# L1221_TOP_V2_3.net
KiCad netlist of a schematic drawn in Altium Designer
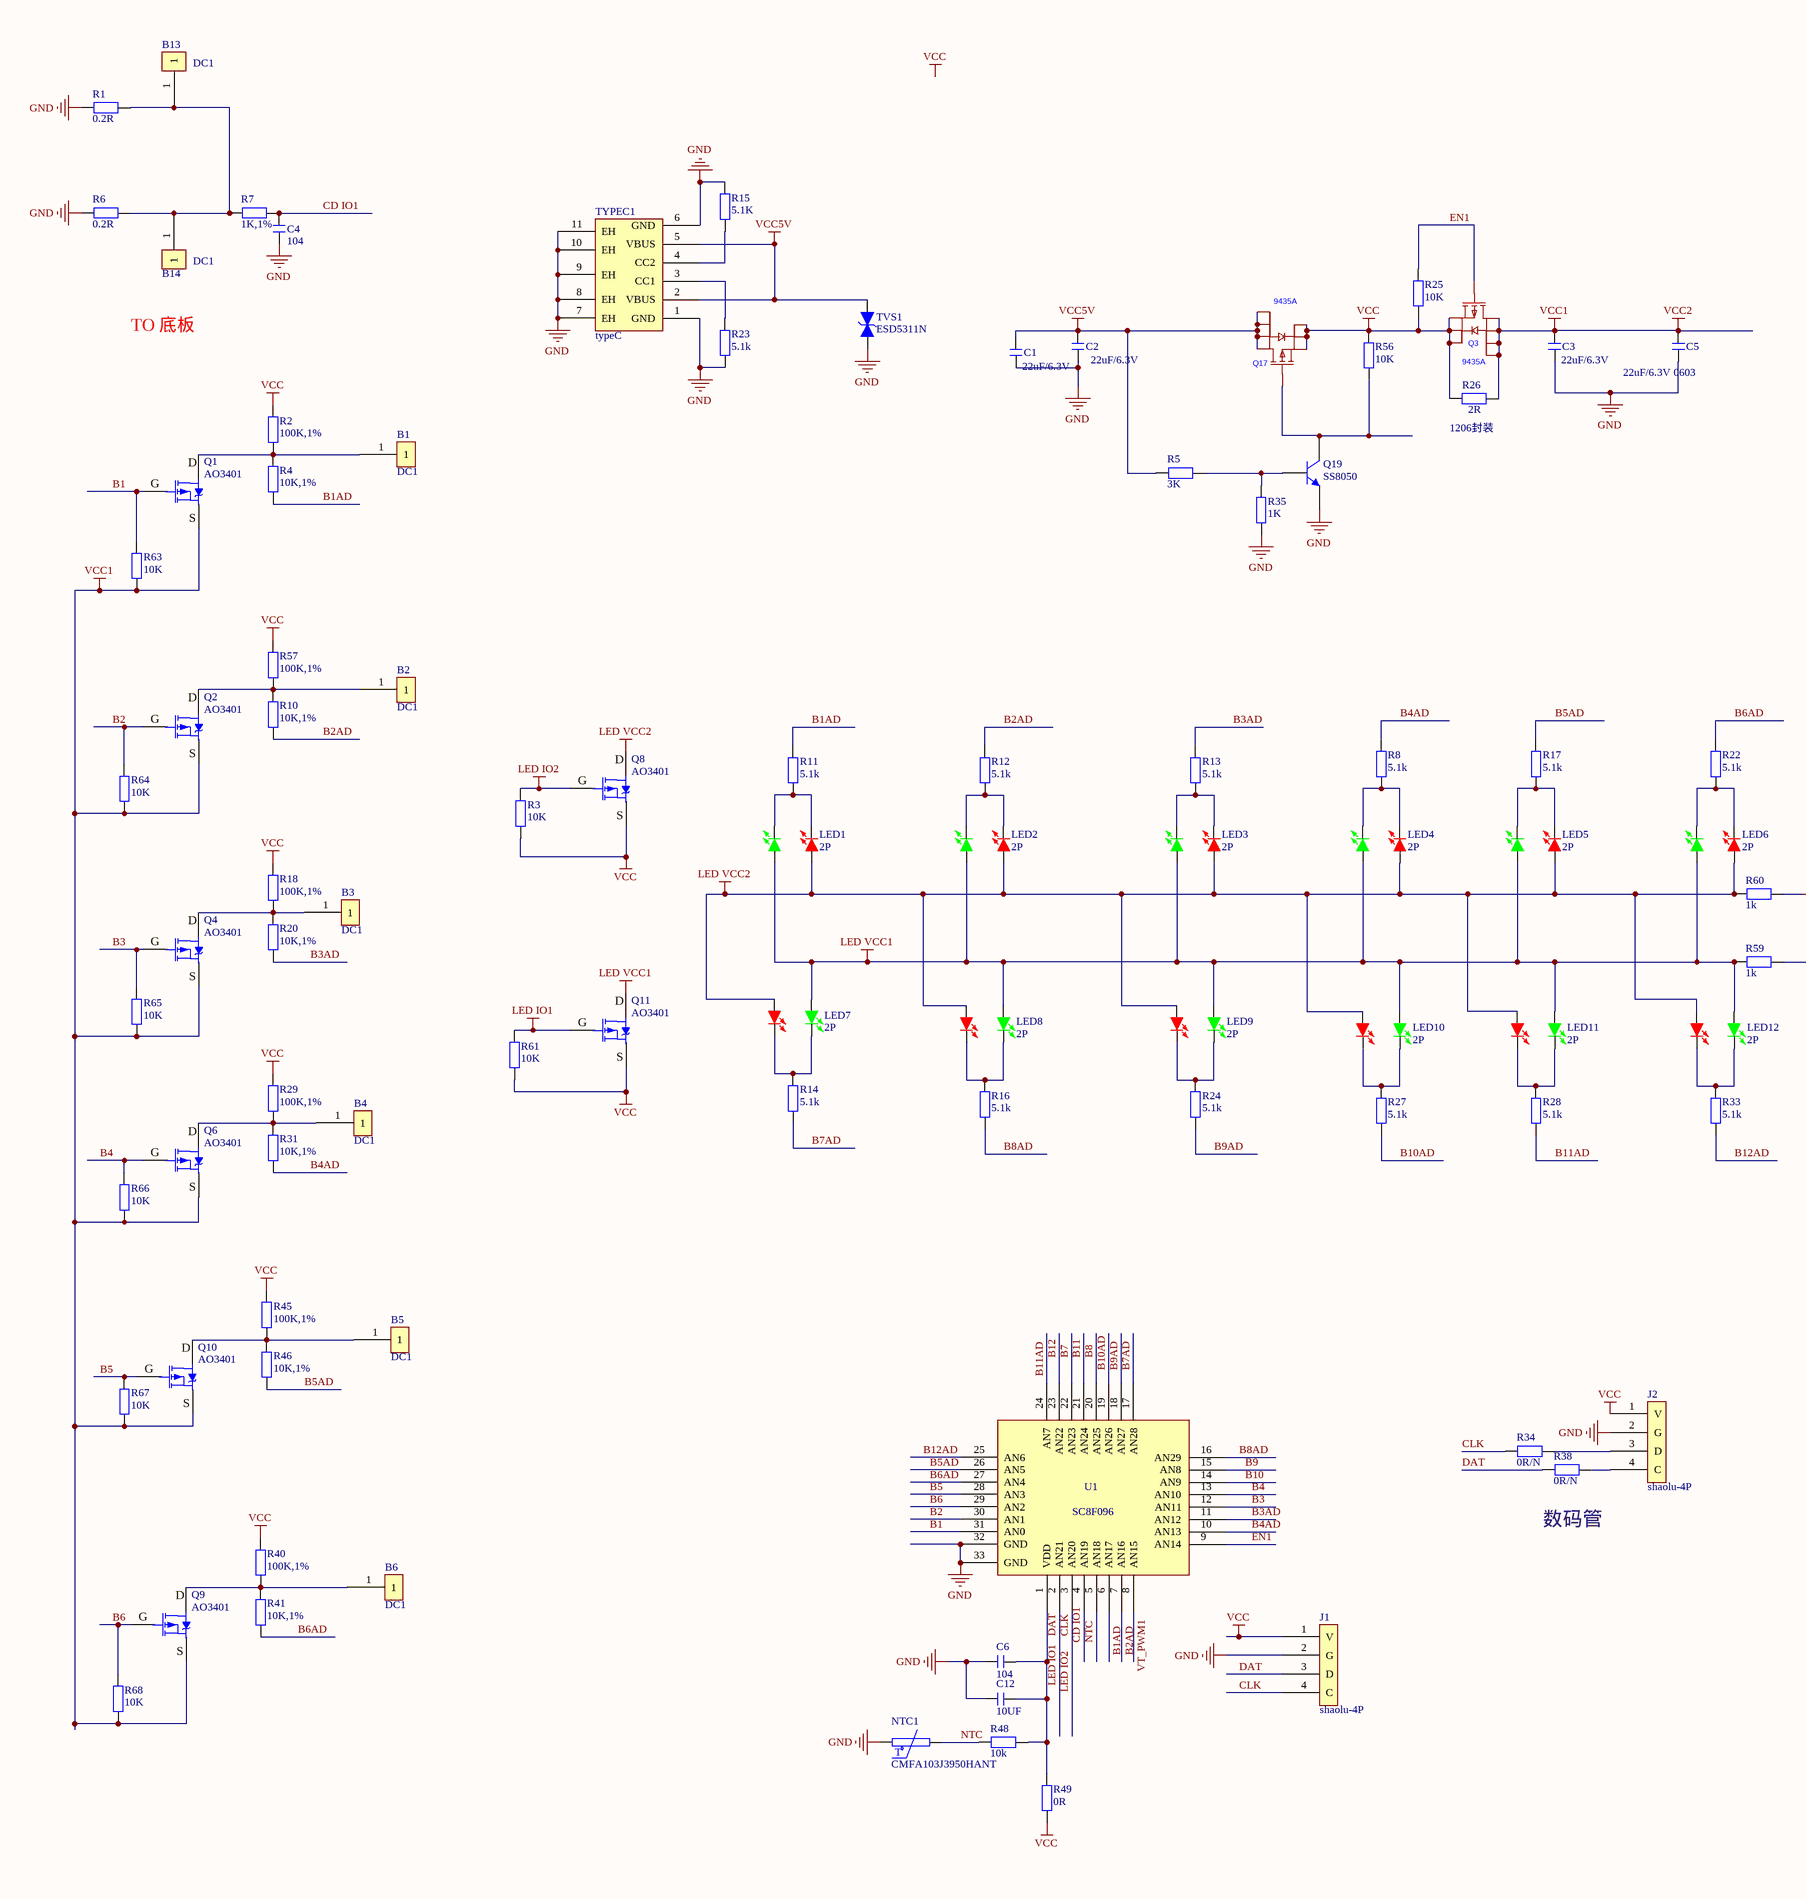
[diagram p0: L1221 TOP V2.3.SchDoc, left]
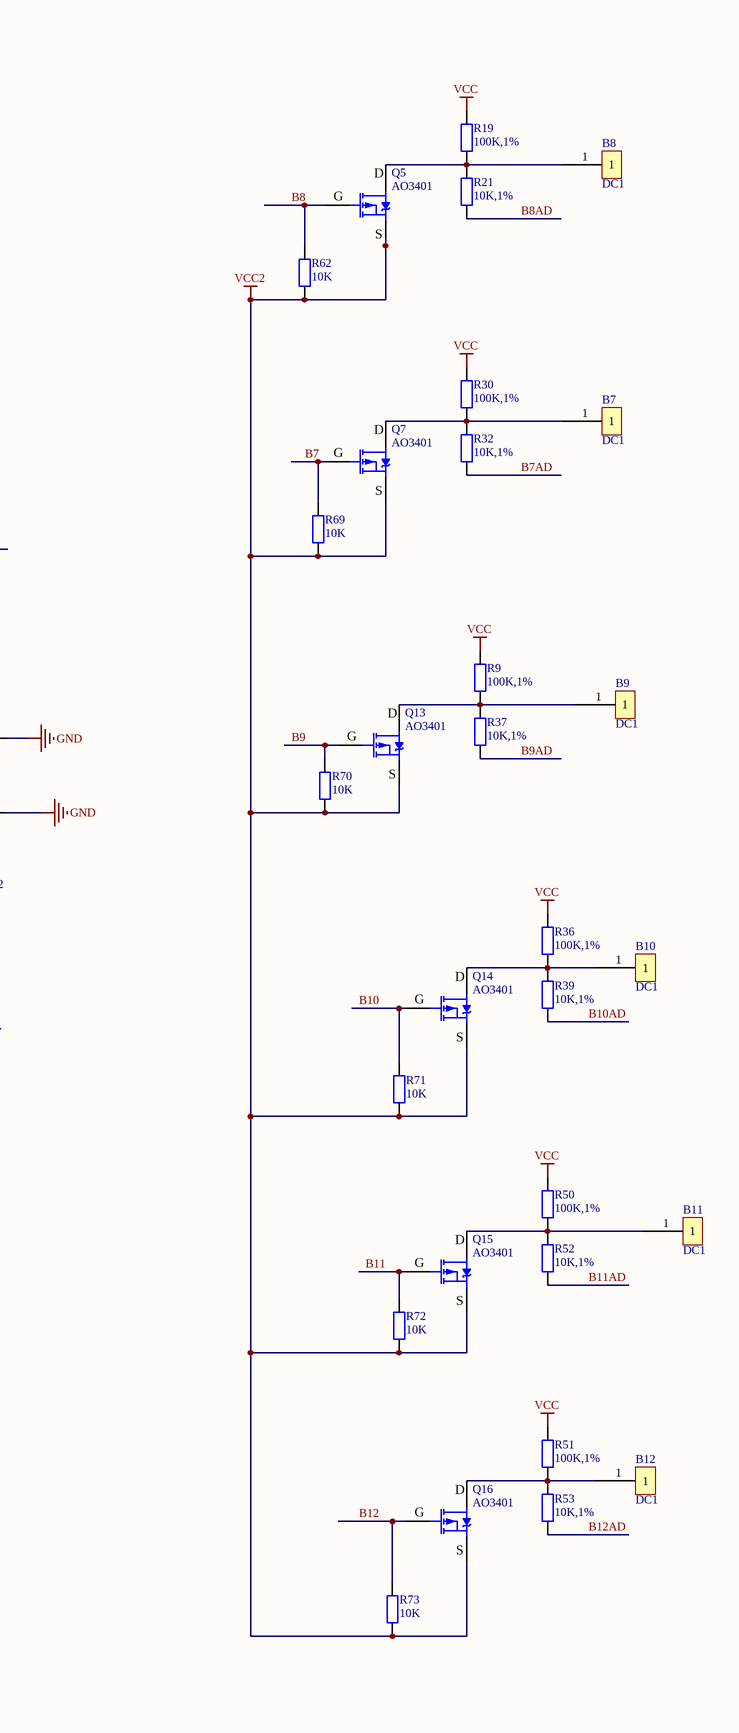
[diagram p1: L1221 TOP V2.3.SchDoc, right]

(export (version "E")
  (design (tool "Eeschema 10.0.6"))
  (components
    (comp (ref "B1") (value "DC1") (footprint "POPOPIN01") (libsource (lib "") (part "dianchi1_1")))
    (comp (ref "B2") (value "DC1") (footprint "POPOPIN01") (libsource (lib "") (part "dianchi1_1")))
    (comp (ref "B3") (value "DC1") (footprint "POPOPIN01") (libsource (lib "") (part "dianchi1_1")))
    (comp (ref "B4") (value "DC1") (footprint "POPOPIN01") (libsource (lib "") (part "dianchi1_1")))
    (comp (ref "B5") (value "DC1") (footprint "POPOPIN01") (libsource (lib "") (part "dianchi1_1")))
    (comp (ref "B6") (value "DC1") (footprint "POPOPIN01") (libsource (lib "") (part "dianchi1_1")))
    (comp (ref "B7") (value "DC1") (footprint "POPOPIN01") (libsource (lib "") (part "dianchi1_1")))
    (comp (ref "B8") (value "DC1") (footprint "POPOPIN01") (libsource (lib "") (part "dianchi1_1")))
    (comp (ref "B9") (value "DC1") (footprint "POPOPIN01") (libsource (lib "") (part "dianchi1_1")))
    (comp (ref "B10") (value "DC1") (footprint "POPOPIN01") (libsource (lib "") (part "dianchi1_1")))
    (comp (ref "B11") (value "DC1") (footprint "POPOPIN01") (libsource (lib "") (part "dianchi1_1")))
    (comp (ref "B12") (value "DC1") (footprint "POPOPIN01") (libsource (lib "") (part "dianchi1_1")))
    (comp (ref "B13") (value "DC1") (footprint "POPOPIN01") (libsource (lib "4.1   - 接口类") (part "dianchi1")))
    (comp (ref "B14") (value "DC1") (footprint "POPOPIN01") (libsource (lib "") (part "dianchi1_2")))
    (comp (ref "C1")
      (value "22uF/6.3V")
      (footprint "0805L")
      (description "无极性贴片电容")
      (libsource (lib "3.1   - 电阻-电容-电感") (part "C"))
    )
    (comp (ref "C2")
      (value "22uF/6.3V")
      (footprint "0805l")
      (description "无极性贴片电容")
      (libsource (lib "3.1   - 电阻-电容-电感") (part "C"))
    )
    (comp (ref "C3")
      (value "22uF/6.3V")
      (footprint "0805l")
      (description "无极性贴片电容")
      (libsource (lib "3.1   - 电阻-电容-电感") (part "C"))
    )
    (comp (ref "C4")
      (value "104")
      (footprint "R0402")
      (description "无极性贴片电容")
      (libsource (lib "3.1   - 电阻-电容-电感") (part "C"))
    )
    (comp (ref "C5")
      (value "22uF/6.3V 0603")
      (footprint "0805l")
      (description "无极性贴片电容")
      (libsource (lib "3.1   - 电阻-电容-电感") (part "C"))
    )
    (comp (ref "C6")
      (value "104")
      (footprint "R0402")
      (description "无极性贴片电容")
      (libsource (lib "3.1   - 电阻-电容-电感") (part "C"))
    )
    (comp (ref "C12")
      (value "10UF")
      (footprint "0603L")
      (description "无极性贴片电容")
      (libsource (lib "3.1   - 电阻-电容-电感") (part "C"))
    )
    (comp (ref "J1")
      (value "shaolu-4P")
      (footprint "shaolu-4P")
      (libsource (lib "4.1   - 接口类") (part "shaolu-4P"))
    )
    (comp (ref "J2")
      (value "shaolu-4P")
      (footprint "W60.5-L48数码管")
      (libsource (lib "4.1   - 接口类") (part "shaolu-4P"))
    )
    (comp (ref "LED1")
      (value "2P")
      (footprint "LED 0606")
      (description "共阴双色LED")
      (libsource (lib "9.1   - LED") (part "LED RG-K"))
    )
    (comp (ref "LED2")
      (value "2P")
      (footprint "LED 0606")
      (description "共阴双色LED")
      (libsource (lib "9.1   - LED") (part "LED RG-K"))
    )
    (comp (ref "LED3")
      (value "2P")
      (footprint "LED 0606")
      (description "共阴双色LED")
      (libsource (lib "9.1   - LED") (part "LED RG-K"))
    )
    (comp (ref "LED4")
      (value "2P")
      (footprint "LED 0606")
      (description "共阴双色LED")
      (libsource (lib "9.1   - LED") (part "LED RG-K"))
    )
    (comp (ref "LED5")
      (value "2P")
      (footprint "LED 0606")
      (description "共阴双色LED")
      (libsource (lib "9.1   - LED") (part "LED RG-K"))
    )
    (comp (ref "LED6")
      (value "2P")
      (footprint "LED 0606")
      (description "共阴双色LED")
      (libsource (lib "9.1   - LED") (part "LED RG-K"))
    )
    (comp (ref "LED7")
      (value "2P")
      (footprint "LED 0606")
      (description "共阴双色LED")
      (libsource (lib "9.1   - LED") (part "LED RG-K"))
    )
    (comp (ref "LED8")
      (value "2P")
      (footprint "LED 0606")
      (description "共阴双色LED")
      (libsource (lib "9.1   - LED") (part "LED RG-K"))
    )
    (comp (ref "LED9")
      (value "2P")
      (footprint "LED 0606")
      (description "共阴双色LED")
      (libsource (lib "9.1   - LED") (part "LED RG-K"))
    )
    (comp (ref "LED10")
      (value "2P")
      (footprint "LED 0606")
      (description "共阴双色LED")
      (libsource (lib "9.1   - LED") (part "LED RG-K"))
    )
    (comp (ref "LED11")
      (value "2P")
      (footprint "LED 0606")
      (description "共阴双色LED")
      (libsource (lib "9.1   - LED") (part "LED RG-K"))
    )
    (comp (ref "LED12")
      (value "2P")
      (footprint "LED 0606")
      (description "共阴双色LED")
      (libsource (lib "9.1   - LED") (part "LED RG-K"))
    )
    (comp (ref "NTC1") (value "CMFA103J3950HANT") (footprint "0603L") (libsource (lib "*") (part "RES2-R")))
    (comp (ref "Q1")
      (value "AO3401")
      (footprint "SOT23-3N")
      (description "P沟道场效应管")
      (libsource (lib "6.1   - 场效应管-可控硅") (part "SI2301"))
    )
    (comp (ref "Q2")
      (value "AO3401")
      (footprint "SOT23-3N")
      (description "P沟道场效应管")
      (libsource (lib "6.1   - 场效应管-可控硅") (part "SI2301"))
    )
    (comp (ref "Q3")
      (value "9435A")
      (footprint "SOP8")
      (fields (field (name "MANUFACTURER") "HL(富海微)"))
      (libsource (lib "altium-import") (part "root_3_9435A_"))
    )
    (comp (ref "Q4")
      (value "AO3401")
      (footprint "SOT23-3N")
      (description "P沟道场效应管")
      (libsource (lib "6.1   - 场效应管-可控硅") (part "SI2301"))
    )
    (comp (ref "Q5")
      (value "AO3401")
      (footprint "SOT23-3N")
      (description "P沟道场效应管")
      (libsource (lib "6.1   - 场效应管-可控硅") (part "SI2301"))
    )
    (comp (ref "Q6")
      (value "AO3401")
      (footprint "SOT23-3N")
      (description "P沟道场效应管")
      (libsource (lib "6.1   - 场效应管-可控硅") (part "SI2301"))
    )
    (comp (ref "Q7")
      (value "AO3401")
      (footprint "SOT23-3N")
      (description "P沟道场效应管")
      (libsource (lib "6.1   - 场效应管-可控硅") (part "SI2301"))
    )
    (comp (ref "Q8")
      (value "AO3401")
      (footprint "SOT23-3N")
      (description "P沟道场效应管")
      (libsource (lib "6.1   - 场效应管-可控硅") (part "SI2301"))
    )
    (comp (ref "Q9")
      (value "AO3401")
      (footprint "SOT23-3N")
      (description "P沟道场效应管")
      (libsource (lib "6.1   - 场效应管-可控硅") (part "SI2301"))
    )
    (comp (ref "Q10")
      (value "AO3401")
      (footprint "SOT23-3N")
      (description "P沟道场效应管")
      (libsource (lib "6.1   - 场效应管-可控硅") (part "SI2301"))
    )
    (comp (ref "Q11")
      (value "AO3401")
      (footprint "SOT23-3N")
      (description "P沟道场效应管")
      (libsource (lib "6.1   - 场效应管-可控硅") (part "SI2301"))
    )
    (comp (ref "Q13")
      (value "AO3401")
      (footprint "SOT23-3N")
      (description "P沟道场效应管")
      (libsource (lib "6.1   - 场效应管-可控硅") (part "SI2301"))
    )
    (comp (ref "Q14")
      (value "AO3401")
      (footprint "SOT23-3N")
      (description "P沟道场效应管")
      (libsource (lib "6.1   - 场效应管-可控硅") (part "SI2301"))
    )
    (comp (ref "Q15")
      (value "AO3401")
      (footprint "SOT23-3N")
      (description "P沟道场效应管")
      (libsource (lib "6.1   - 场效应管-可控硅") (part "SI2301"))
    )
    (comp (ref "Q16")
      (value "AO3401")
      (footprint "SOT23-3N")
      (description "P沟道场效应管")
      (libsource (lib "6.1   - 场效应管-可控硅") (part "SI2301"))
    )
    (comp (ref "Q17")
      (value "9435A")
      (footprint "SOP8")
      (fields (field (name "MANUFACTURER") "HL(富海微)"))
      (libsource (lib "altium-import") (part "root_1_9435A_"))
    )
    (comp (ref "Q19")
      (value "SS8050")
      (footprint "SOT23-3N")
      (description "NPN Bipolar Transistor")
      (libsource (lib "Miscellaneous Devices") (part "QNPN"))
    )
    (comp (ref "R1")
      (value "0.2R")
      (footprint "R 1206_L")
      (description "贴片电阻")
      (libsource (lib "3.1   - 电阻-电容-电感") (part "R"))
    )
    (comp (ref "R2")
      (value "100K,1%")
      (footprint "R0402")
      (description "贴片电阻")
      (fields (field (name "TOLERANCE") "±5%"))
      (libsource (lib "3.1   - 电阻-电容-电感") (part "R"))
    )
    (comp (ref "R3")
      (value "10K")
      (footprint "R0402")
      (description "贴片电阻")
      (fields (field (name "TOLERANCE") "±5%") (field (name "TOLERANCE_1") "Tolerance"))
      (libsource (lib "3.1   - 电阻-电容-电感") (part "R"))
    )
    (comp (ref "R4")
      (value "10K,1%")
      (footprint "R0402")
      (description "贴片电阻")
      (fields (field (name "TOLERANCE") "±1%"))
      (libsource (lib "3.1   - 电阻-电容-电感") (part "R"))
    )
    (comp (ref "R5")
      (value "3K")
      (footprint "R0402")
      (description "贴片电阻")
      (libsource (lib "3.1   - 电阻-电容-电感") (part "R"))
    )
    (comp (ref "R6")
      (value "0.2R")
      (footprint "R 1206_L")
      (description "贴片电阻")
      (libsource (lib "3.1   - 电阻-电容-电感") (part "R"))
    )
    (comp (ref "R7")
      (value "1K,1%")
      (footprint "R0402")
      (description "贴片电阻")
      (libsource (lib "3.1   - 电阻-电容-电感") (part "R"))
    )
    (comp (ref "R8")
      (value "5.1k")
      (footprint "R0402")
      (description "贴片电阻")
      (fields (field (name "TOLERANCE") "±5%") (field (name "TOLERANCE_1") "Tolerance"))
      (libsource (lib "3.1   - 电阻-电容-电感") (part "R"))
    )
    (comp (ref "R9")
      (value "100K,1%")
      (footprint "R0402")
      (description "贴片电阻")
      (fields (field (name "TOLERANCE") "±5%"))
      (libsource (lib "3.1   - 电阻-电容-电感") (part "R"))
    )
    (comp (ref "R10")
      (value "10K,1%")
      (footprint "R0402")
      (description "贴片电阻")
      (fields (field (name "TOLERANCE") "±1%"))
      (libsource (lib "3.1   - 电阻-电容-电感") (part "R"))
    )
    (comp (ref "R11")
      (value "5.1k")
      (footprint "R0402")
      (description "贴片电阻")
      (fields (field (name "TOLERANCE") "±5%") (field (name "TOLERANCE_1") "Tolerance"))
      (libsource (lib "3.1   - 电阻-电容-电感") (part "R"))
    )
    (comp (ref "R12")
      (value "5.1k")
      (footprint "R0402")
      (description "贴片电阻")
      (fields (field (name "TOLERANCE") "±5%") (field (name "TOLERANCE_1") "Tolerance"))
      (libsource (lib "3.1   - 电阻-电容-电感") (part "R"))
    )
    (comp (ref "R13")
      (value "5.1k")
      (footprint "R0402")
      (description "贴片电阻")
      (fields (field (name "TOLERANCE") "±5%") (field (name "TOLERANCE_1") "Tolerance"))
      (libsource (lib "3.1   - 电阻-电容-电感") (part "R"))
    )
    (comp (ref "R14")
      (value "5.1k")
      (footprint "R0402")
      (description "贴片电阻")
      (fields (field (name "TOLERANCE") "±5%") (field (name "TOLERANCE_1") "Tolerance"))
      (libsource (lib "3.1   - 电阻-电容-电感") (part "R"))
    )
    (comp (ref "R15")
      (value "5.1K")
      (footprint "r0402")
      (description "贴片电阻")
      (libsource (lib "3.1   - 电阻-电容-电感") (part "R"))
    )
    (comp (ref "R16")
      (value "5.1k")
      (footprint "R0402")
      (description "贴片电阻")
      (fields (field (name "TOLERANCE") "±5%") (field (name "TOLERANCE_1") "Tolerance"))
      (libsource (lib "3.1   - 电阻-电容-电感") (part "R"))
    )
    (comp (ref "R17")
      (value "5.1k")
      (footprint "R0402")
      (description "贴片电阻")
      (fields (field (name "TOLERANCE") "±5%") (field (name "TOLERANCE_1") "Tolerance"))
      (libsource (lib "3.1   - 电阻-电容-电感") (part "R"))
    )
    (comp (ref "R18")
      (value "100K,1%")
      (footprint "R0402")
      (description "贴片电阻")
      (fields (field (name "TOLERANCE") "Tolerance") (field (name "TOLERANCE_1") "±5%"))
      (libsource (lib "3.1   - 电阻-电容-电感") (part "R"))
    )
    (comp (ref "R19")
      (value "100K,1%")
      (footprint "R0402")
      (description "贴片电阻")
      (fields (field (name "TOLERANCE") "±5%"))
      (libsource (lib "3.1   - 电阻-电容-电感") (part "R"))
    )
    (comp (ref "R20")
      (value "10K,1%")
      (footprint "R0402")
      (description "贴片电阻")
      (fields (field (name "TOLERANCE") "±1%"))
      (libsource (lib "3.1   - 电阻-电容-电感") (part "R"))
    )
    (comp (ref "R21")
      (value "10K,1%")
      (footprint "R0402")
      (description "贴片电阻")
      (fields (field (name "TOLERANCE") "±1%"))
      (libsource (lib "3.1   - 电阻-电容-电感") (part "R"))
    )
    (comp (ref "R22")
      (value "5.1k")
      (footprint "R0402")
      (description "贴片电阻")
      (fields (field (name "TOLERANCE") "±5%") (field (name "TOLERANCE_1") "Tolerance"))
      (libsource (lib "3.1   - 电阻-电容-电感") (part "R"))
    )
    (comp (ref "R23")
      (value "5.1k")
      (footprint "R0402")
      (description "贴片电阻")
      (libsource (lib "3.1   - 电阻-电容-电感") (part "R"))
    )
    (comp (ref "R24")
      (value "5.1k")
      (footprint "R0402")
      (description "贴片电阻")
      (fields (field (name "TOLERANCE") "±5%") (field (name "TOLERANCE_1") "Tolerance"))
      (libsource (lib "3.1   - 电阻-电容-电感") (part "R"))
    )
    (comp (ref "R25")
      (value "10K")
      (footprint "R0402")
      (description "贴片电阻")
      (fields (field (name "TOLERANCE") "±5%"))
      (libsource (lib "3.1   - 电阻-电容-电感") (part "R"))
    )
    (comp (ref "R26")
      (value "2R")
      (footprint "R 1206_L")
      (description "贴片电阻")
      (fields (field (name "TOLERANCE") "±5%"))
      (libsource (lib "3.1   - 电阻-电容-电感") (part "R"))
    )
    (comp (ref "R27")
      (value "5.1k")
      (footprint "R0402")
      (description "贴片电阻")
      (fields (field (name "TOLERANCE") "±5%") (field (name "TOLERANCE_1") "Tolerance"))
      (libsource (lib "3.1   - 电阻-电容-电感") (part "R"))
    )
    (comp (ref "R28")
      (value "5.1k")
      (footprint "R0402")
      (description "贴片电阻")
      (fields (field (name "TOLERANCE") "±5%") (field (name "TOLERANCE_1") "Tolerance"))
      (libsource (lib "3.1   - 电阻-电容-电感") (part "R"))
    )
    (comp (ref "R29")
      (value "100K,1%")
      (footprint "R0402")
      (description "贴片电阻")
      (fields (field (name "TOLERANCE") "±5%"))
      (libsource (lib "3.1   - 电阻-电容-电感") (part "R"))
    )
    (comp (ref "R30")
      (value "100K,1%")
      (footprint "R0402")
      (description "贴片电阻")
      (fields (field (name "TOLERANCE") "±5%"))
      (libsource (lib "3.1   - 电阻-电容-电感") (part "R"))
    )
    (comp (ref "R31")
      (value "10K,1%")
      (footprint "R0402")
      (description "贴片电阻")
      (fields (field (name "TOLERANCE") "±1%"))
      (libsource (lib "3.1   - 电阻-电容-电感") (part "R"))
    )
    (comp (ref "R32")
      (value "10K,1%")
      (footprint "R0402")
      (description "贴片电阻")
      (fields (field (name "TOLERANCE") "±1%"))
      (libsource (lib "3.1   - 电阻-电容-电感") (part "R"))
    )
    (comp (ref "R33")
      (value "5.1k")
      (footprint "R0402")
      (description "贴片电阻")
      (fields (field (name "TOLERANCE") "±5%") (field (name "TOLERANCE_1") "Tolerance"))
      (libsource (lib "3.1   - 电阻-电容-电感") (part "R"))
    )
    (comp (ref "R34")
      (value "0R/N")
      (footprint "R0402")
      (description "贴片电阻")
      (libsource (lib "3.1   - 电阻-电容-电感") (part "R"))
    )
    (comp (ref "R35")
      (value "1K")
      (footprint "R0402")
      (description "贴片电阻")
      (libsource (lib "3.1   - 电阻-电容-电感") (part "R"))
    )
    (comp (ref "R36")
      (value "100K,1%")
      (footprint "R0402")
      (description "贴片电阻")
      (fields (field (name "TOLERANCE") "±5%"))
      (libsource (lib "3.1   - 电阻-电容-电感") (part "R"))
    )
    (comp (ref "R37")
      (value "10K,1%")
      (footprint "R0402")
      (description "贴片电阻")
      (fields (field (name "TOLERANCE") "±1%"))
      (libsource (lib "3.1   - 电阻-电容-电感") (part "R"))
    )
    (comp (ref "R38")
      (value "0R/N")
      (footprint "R0402")
      (description "贴片电阻")
      (libsource (lib "3.1   - 电阻-电容-电感") (part "R"))
    )
    (comp (ref "R39")
      (value "10K,1%")
      (footprint "R0402")
      (description "贴片电阻")
      (fields (field (name "TOLERANCE") "±1%"))
      (libsource (lib "3.1   - 电阻-电容-电感") (part "R"))
    )
    (comp (ref "R40")
      (value "100K,1%")
      (footprint "R0402")
      (description "贴片电阻")
      (fields (field (name "TOLERANCE") "±5%"))
      (libsource (lib "3.1   - 电阻-电容-电感") (part "R"))
    )
    (comp (ref "R41")
      (value "10K,1%")
      (footprint "R0402")
      (description "贴片电阻")
      (fields (field (name "TOLERANCE") "±1%"))
      (libsource (lib "3.1   - 电阻-电容-电感") (part "R"))
    )
    (comp (ref "R45")
      (value "100K,1%")
      (footprint "R0402")
      (description "贴片电阻")
      (fields (field (name "TOLERANCE") "±5%"))
      (libsource (lib "3.1   - 电阻-电容-电感") (part "R"))
    )
    (comp (ref "R46")
      (value "10K,1%")
      (footprint "R0402")
      (description "贴片电阻")
      (fields (field (name "TOLERANCE") "±1%"))
      (libsource (lib "3.1   - 电阻-电容-电感") (part "R"))
    )
    (comp (ref "R48")
      (value "10k")
      (footprint "R0402")
      (description "贴片电阻")
      (fields (field (name "TOLERANCE") "Tolerance") (field (name "TOLERANCE_1") "±5%"))
      (libsource (lib "3.1   - 电阻-电容-电感") (part "R"))
    )
    (comp (ref "R49")
      (value "0R")
      (footprint "R0402")
      (description "贴片电阻")
      (fields (field (name "TOLERANCE") "Tolerance") (field (name "TOLERANCE_1") "±5%"))
      (libsource (lib "3.1   - 电阻-电容-电感") (part "R"))
    )
    (comp (ref "R50")
      (value "100K,1%")
      (footprint "R0402")
      (description "贴片电阻")
      (fields (field (name "TOLERANCE") "±5%"))
      (libsource (lib "3.1   - 电阻-电容-电感") (part "R"))
    )
    (comp (ref "R51")
      (value "100K,1%")
      (footprint "R0402")
      (description "贴片电阻")
      (fields (field (name "TOLERANCE") "±5%"))
      (libsource (lib "3.1   - 电阻-电容-电感") (part "R"))
    )
    (comp (ref "R52")
      (value "10K,1%")
      (footprint "R0402")
      (description "贴片电阻")
      (fields (field (name "TOLERANCE") "±1%"))
      (libsource (lib "3.1   - 电阻-电容-电感") (part "R"))
    )
    (comp (ref "R53")
      (value "10K,1%")
      (footprint "R0402")
      (description "贴片电阻")
      (fields (field (name "TOLERANCE") "±1%"))
      (libsource (lib "3.1   - 电阻-电容-电感") (part "R"))
    )
    (comp (ref "R56")
      (value "10K")
      (footprint "R0402")
      (description "贴片电阻")
      (fields (field (name "TOLERANCE") "±5%"))
      (libsource (lib "3.1   - 电阻-电容-电感") (part "R"))
    )
    (comp (ref "R57")
      (value "100K,1%")
      (footprint "R0402")
      (description "贴片电阻")
      (fields (field (name "TOLERANCE") "Tolerance") (field (name "TOLERANCE_1") "±5%"))
      (libsource (lib "3.1   - 电阻-电容-电感") (part "R"))
    )
    (comp (ref "R59")
      (value "1k")
      (footprint "R0402")
      (description "贴片电阻")
      (fields (field (name "TOLERANCE") "Tolerance") (field (name "TOLERANCE_1") "±5%"))
      (libsource (lib "3.1   - 电阻-电容-电感") (part "R"))
    )
    (comp (ref "R60")
      (value "1k")
      (footprint "R0402")
      (description "贴片电阻")
      (fields (field (name "TOLERANCE") "Tolerance") (field (name "TOLERANCE_1") "±5%"))
      (libsource (lib "3.1   - 电阻-电容-电感") (part "R"))
    )
    (comp (ref "R61")
      (value "10K")
      (footprint "R0402")
      (description "贴片电阻")
      (fields (field (name "TOLERANCE") "±5%") (field (name "TOLERANCE_1") "Tolerance"))
      (libsource (lib "3.1   - 电阻-电容-电感") (part "R"))
    )
    (comp (ref "R62")
      (value "10K")
      (footprint "R0402")
      (description "贴片电阻")
      (fields (field (name "TOLERANCE") "±5%"))
      (libsource (lib "3.1   - 电阻-电容-电感") (part "R"))
    )
    (comp (ref "R63")
      (value "10K")
      (footprint "R0402")
      (description "贴片电阻")
      (fields (field (name "TOLERANCE") "±5%"))
      (libsource (lib "3.1   - 电阻-电容-电感") (part "R"))
    )
    (comp (ref "R64")
      (value "10K")
      (footprint "R0402")
      (description "贴片电阻")
      (fields (field (name "TOLERANCE") "±5%"))
      (libsource (lib "3.1   - 电阻-电容-电感") (part "R"))
    )
    (comp (ref "R65")
      (value "10K")
      (footprint "R0402")
      (description "贴片电阻")
      (fields (field (name "TOLERANCE") "±5%"))
      (libsource (lib "3.1   - 电阻-电容-电感") (part "R"))
    )
    (comp (ref "R66")
      (value "10K")
      (footprint "R0402")
      (description "贴片电阻")
      (fields (field (name "TOLERANCE") "±5%"))
      (libsource (lib "3.1   - 电阻-电容-电感") (part "R"))
    )
    (comp (ref "R67")
      (value "10K")
      (footprint "R0402")
      (description "贴片电阻")
      (fields (field (name "TOLERANCE") "±5%"))
      (libsource (lib "3.1   - 电阻-电容-电感") (part "R"))
    )
    (comp (ref "R68")
      (value "10K")
      (footprint "R0402")
      (description "贴片电阻")
      (fields (field (name "TOLERANCE") "±5%"))
      (libsource (lib "3.1   - 电阻-电容-电感") (part "R"))
    )
    (comp (ref "R69")
      (value "10K")
      (footprint "R0402")
      (description "贴片电阻")
      (fields (field (name "TOLERANCE") "±5%"))
      (libsource (lib "3.1   - 电阻-电容-电感") (part "R"))
    )
    (comp (ref "R70")
      (value "10K")
      (footprint "R0402")
      (description "贴片电阻")
      (fields (field (name "TOLERANCE") "±5%"))
      (libsource (lib "3.1   - 电阻-电容-电感") (part "R"))
    )
    (comp (ref "R71")
      (value "10K")
      (footprint "R0402")
      (description "贴片电阻")
      (fields (field (name "TOLERANCE") "±5%"))
      (libsource (lib "3.1   - 电阻-电容-电感") (part "R"))
    )
    (comp (ref "R72")
      (value "10K")
      (footprint "R0402")
      (description "贴片电阻")
      (fields (field (name "TOLERANCE") "±5%"))
      (libsource (lib "3.1   - 电阻-电容-电感") (part "R"))
    )
    (comp (ref "R73")
      (value "10K")
      (footprint "R0402")
      (description "贴片电阻")
      (fields (field (name "TOLERANCE") "±5%"))
      (libsource (lib "3.1   - 电阻-电容-电感") (part "R"))
    )
    (comp (ref "TVS1") (value "ESD5311N") (footprint "DFN1006-2L") (libsource (lib "*") (part "DIODE-3")))
    (comp (ref "TYPEC1") (value "typeC") (footprint "typeC") (libsource (lib "4.1   - 接口类") (part "typeC")))
    (comp (ref "U1")
      (value "SC8F096")
      (footprint "QFN-32-4*4")
      (libsource (lib "1.1   - IC芯片") (part "SC8F096AD832NPR"))
    )
  )
  (nets
    (net (code "1") (name "/B1") (class "Default")
      (node (ref "Q1") (pin "1") (pinfunction "G_1") (pintype "passive"))
      (node (ref "R63") (pin "2") (pinfunction "2_2") (pintype "passive"))
      (node (ref "U1") (pin "31") (pinfunction "AN0_31") (pintype "passive"))
    )
    (net (code "2") (name "/B1AD") (class "Default")
      (node (ref "R11") (pin "2") (pinfunction "2_2") (pintype "passive"))
      (node (ref "R4") (pin "1") (pinfunction "1_1") (pintype "passive"))
      (node (ref "U1") (pin "6") (pinfunction "AN17_6") (pintype "passive"))
    )
    (net (code "3") (name "/B2") (class "Default")
      (node (ref "Q2") (pin "1") (pinfunction "G_1") (pintype "passive"))
      (node (ref "R64") (pin "2") (pinfunction "2_2") (pintype "passive"))
      (node (ref "U1") (pin "30") (pinfunction "AN1_30") (pintype "passive"))
    )
    (net (code "4") (name "/B2AD") (class "Default")
      (node (ref "R10") (pin "1") (pinfunction "1_1") (pintype "passive"))
      (node (ref "R12") (pin "2") (pinfunction "2_2") (pintype "passive"))
      (node (ref "U1") (pin "7") (pinfunction "AN16_7") (pintype "passive"))
    )
    (net (code "5") (name "/B3") (class "Default")
      (node (ref "Q4") (pin "1") (pinfunction "G_1") (pintype "passive"))
      (node (ref "R65") (pin "2") (pinfunction "2_2") (pintype "passive"))
      (node (ref "U1") (pin "12") (pinfunction "AN11_12") (pintype "passive"))
    )
    (net (code "6") (name "/B3AD") (class "Default")
      (node (ref "R13") (pin "2") (pinfunction "2_2") (pintype "passive"))
      (node (ref "R20") (pin "1") (pinfunction "1_1") (pintype "passive"))
      (node (ref "U1") (pin "11") (pinfunction "AN12_11") (pintype "passive"))
    )
    (net (code "7") (name "/B4") (class "Default")
      (node (ref "Q6") (pin "1") (pinfunction "G_1") (pintype "passive"))
      (node (ref "R66") (pin "2") (pinfunction "2_2") (pintype "passive"))
      (node (ref "U1") (pin "13") (pinfunction "AN10_13") (pintype "passive"))
    )
    (net (code "8") (name "/B4AD") (class "Default")
      (node (ref "R31") (pin "1") (pinfunction "1_1") (pintype "passive"))
      (node (ref "R8") (pin "2") (pinfunction "2_2") (pintype "passive"))
      (node (ref "U1") (pin "10") (pinfunction "AN13_10") (pintype "passive"))
    )
    (net (code "9") (name "/B5") (class "Default")
      (node (ref "Q10") (pin "1") (pinfunction "G_1") (pintype "passive"))
      (node (ref "R67") (pin "2") (pinfunction "2_2") (pintype "passive"))
      (node (ref "U1") (pin "28") (pinfunction "AN3_28") (pintype "passive"))
    )
    (net (code "10") (name "/B5AD") (class "Default")
      (node (ref "R17") (pin "2") (pinfunction "2_2") (pintype "passive"))
      (node (ref "R46") (pin "1") (pinfunction "1_1") (pintype "passive"))
      (node (ref "U1") (pin "26") (pinfunction "AN5_26") (pintype "passive"))
    )
    (net (code "11") (name "/B6") (class "Default")
      (node (ref "Q9") (pin "1") (pinfunction "G_1") (pintype "passive"))
      (node (ref "R68") (pin "2") (pinfunction "2_2") (pintype "passive"))
      (node (ref "U1") (pin "29") (pinfunction "AN2_29") (pintype "passive"))
    )
    (net (code "12") (name "/B6AD") (class "Default")
      (node (ref "R22") (pin "2") (pinfunction "2_2") (pintype "passive"))
      (node (ref "R41") (pin "1") (pinfunction "1_1") (pintype "passive"))
      (node (ref "U1") (pin "27") (pinfunction "AN4_27") (pintype "passive"))
    )
    (net (code "13") (name "/B7") (class "Default")
      (node (ref "Q7") (pin "1") (pinfunction "G_1") (pintype "passive"))
      (node (ref "R69") (pin "2") (pinfunction "2_2") (pintype "passive"))
      (node (ref "U1") (pin "22") (pinfunction "AN23_22") (pintype "passive"))
    )
    (net (code "14") (name "/B7AD") (class "Default")
      (node (ref "R14") (pin "1") (pinfunction "1_1") (pintype "passive"))
      (node (ref "R32") (pin "1") (pinfunction "1_1") (pintype "passive"))
      (node (ref "U1") (pin "17") (pinfunction "AN28_17") (pintype "passive"))
    )
    (net (code "15") (name "/B8") (class "Default")
      (node (ref "Q5") (pin "1") (pinfunction "G_1") (pintype "passive"))
      (node (ref "R62") (pin "2") (pinfunction "2_2") (pintype "passive"))
      (node (ref "U1") (pin "20") (pinfunction "AN25_20") (pintype "passive"))
    )
    (net (code "16") (name "/B8AD") (class "Default")
      (node (ref "R16") (pin "1") (pinfunction "1_1") (pintype "passive"))
      (node (ref "R21") (pin "1") (pinfunction "1_1") (pintype "passive"))
      (node (ref "U1") (pin "16") (pinfunction "AN29_16") (pintype "passive"))
    )
    (net (code "17") (name "/B9") (class "Default")
      (node (ref "Q13") (pin "1") (pinfunction "G_1") (pintype "passive"))
      (node (ref "R70") (pin "2") (pinfunction "2_2") (pintype "passive"))
      (node (ref "U1") (pin "15") (pinfunction "AN8_15") (pintype "passive"))
    )
    (net (code "18") (name "/B9AD") (class "Default")
      (node (ref "R24") (pin "1") (pinfunction "1_1") (pintype "passive"))
      (node (ref "R37") (pin "1") (pinfunction "1_1") (pintype "passive"))
      (node (ref "U1") (pin "18") (pinfunction "AN27_18") (pintype "passive"))
    )
    (net (code "19") (name "/B10") (class "Default")
      (node (ref "Q14") (pin "1") (pinfunction "G_1") (pintype "passive"))
      (node (ref "R71") (pin "2") (pinfunction "2_2") (pintype "passive"))
      (node (ref "U1") (pin "14") (pinfunction "AN9_14") (pintype "passive"))
    )
    (net (code "20") (name "/B10AD") (class "Default")
      (node (ref "R27") (pin "1") (pinfunction "1_1") (pintype "passive"))
      (node (ref "R39") (pin "1") (pinfunction "1_1") (pintype "passive"))
      (node (ref "U1") (pin "19") (pinfunction "AN26_19") (pintype "passive"))
    )
    (net (code "21") (name "/B11") (class "Default")
      (node (ref "Q15") (pin "1") (pinfunction "G_1") (pintype "passive"))
      (node (ref "R72") (pin "2") (pinfunction "2_2") (pintype "passive"))
      (node (ref "U1") (pin "21") (pinfunction "AN24_21") (pintype "passive"))
    )
    (net (code "22") (name "/B11AD") (class "Default")
      (node (ref "R28") (pin "1") (pinfunction "1_1") (pintype "passive"))
      (node (ref "R52") (pin "1") (pinfunction "1_1") (pintype "passive"))
      (node (ref "U1") (pin "24") (pinfunction "AN7_24") (pintype "passive"))
    )
    (net (code "23") (name "/B12") (class "Default")
      (node (ref "Q16") (pin "1") (pinfunction "G_1") (pintype "passive"))
      (node (ref "R73") (pin "2") (pinfunction "2_2") (pintype "passive"))
      (node (ref "U1") (pin "23") (pinfunction "AN22_23") (pintype "passive"))
    )
    (net (code "24") (name "/B12AD") (class "Default")
      (node (ref "R33") (pin "1") (pinfunction "1_1") (pintype "passive"))
      (node (ref "R53") (pin "1") (pinfunction "1_1") (pintype "passive"))
      (node (ref "U1") (pin "25") (pinfunction "AN6_25") (pintype "passive"))
    )
    (net (code "25") (name "/CD IO1") (class "Default")
      (node (ref "C4") (pin "2") (pinfunction "2_2") (pintype "passive"))
      (node (ref "R7") (pin "2") (pinfunction "2_2") (pintype "passive"))
      (node (ref "U1") (pin "4") (pinfunction "AN19_4") (pintype "passive"))
    )
    (net (code "26") (name "/EN1") (class "Default")
      (node (ref "Q3") (pin "4") (pinfunction "G_4") (pintype "passive"))
      (node (ref "R25") (pin "2") (pinfunction "2_2") (pintype "passive"))
      (node (ref "U1") (pin "9") (pinfunction "AN14_9") (pintype "passive"))
    )
    (net (code "27") (name "/NTC") (class "Default")
      (node (ref "NTC1") (pin "2") (pinfunction "2_2") (pintype "passive"))
      (node (ref "R48") (pin "2") (pinfunction "2_2") (pintype "passive"))
      (node (ref "U1") (pin "5") (pinfunction "AN18_5") (pintype "passive"))
    )
    (net (code "28") (name "/VT_PWM1") (class "Default")
      (node (ref "U1") (pin "8") (pinfunction "AN15_8") (pintype "passive"))
    )
    (net (code "29") (name "GND") (class "Default")
      (node (ref "C1") (pin "1") (pinfunction "1_1") (pintype "passive"))
      (node (ref "C12") (pin "1") (pinfunction "1_1") (pintype "passive"))
      (node (ref "C2") (pin "1") (pinfunction "1_1") (pintype "passive"))
      (node (ref "C3") (pin "1") (pinfunction "1_1") (pintype "passive"))
      (node (ref "C4") (pin "1") (pinfunction "1_1") (pintype "passive"))
      (node (ref "C5") (pin "1") (pinfunction "1_1") (pintype "passive"))
      (node (ref "C6") (pin "1") (pinfunction "1_1") (pintype "passive"))
      (node (ref "J1") (pin "2") (pinfunction "G_2") (pintype "passive"))
      (node (ref "J2") (pin "2") (pinfunction "G_2") (pintype "passive"))
      (node (ref "NTC1") (pin "1") (pinfunction "1_1") (pintype "passive"))
      (node (ref "Q19") (pin "2") (pinfunction "E_2") (pintype "passive"))
      (node (ref "R1") (pin "1") (pinfunction "1_1") (pintype "passive"))
      (node (ref "R15") (pin "2") (pinfunction "2_2") (pintype "passive"))
      (node (ref "R23") (pin "1") (pinfunction "1_1") (pintype "passive"))
      (node (ref "R35") (pin "1") (pinfunction "1_1") (pintype "passive"))
      (node (ref "R59") (pin "1") (pinfunction "1_1") (pintype "passive"))
      (node (ref "R6") (pin "1") (pinfunction "1_1") (pintype "passive"))
      (node (ref "R60") (pin "2") (pinfunction "2_2") (pintype "passive"))
      (node (ref "TVS1") (pin "1") (pinfunction "A_1") (pintype "passive"))
      (node (ref "TYPEC1") (pin "1") (pinfunction "GND_1") (pintype "passive"))
      (node (ref "TYPEC1") (pin "10") (pinfunction "EH_10") (pintype "passive"))
      (node (ref "TYPEC1") (pin "11") (pinfunction "EH_11") (pintype "passive"))
      (node (ref "TYPEC1") (pin "6") (pinfunction "GND_6") (pintype "passive"))
      (node (ref "TYPEC1") (pin "7") (pinfunction "EH_7") (pintype "passive"))
      (node (ref "TYPEC1") (pin "8") (pinfunction "EH_8") (pintype "passive"))
      (node (ref "TYPEC1") (pin "9") (pinfunction "EH_9") (pintype "passive"))
      (node (ref "U1") (pin "32") (pinfunction "GND_32") (pintype "passive"))
      (node (ref "U1") (pin "33") (pinfunction "GND_33") (pintype "passive"))
    )
    (net (code "30") (name "LED IO1") (class "Default")
      (node (ref "J1") (pin "3") (pinfunction "D_3") (pintype "passive"))
      (node (ref "Q11") (pin "1") (pinfunction "G_1") (pintype "passive"))
      (node (ref "R38") (pin "2") (pinfunction "2_2") (pintype "passive"))
      (node (ref "R61") (pin "2") (pinfunction "2_2") (pintype "passive"))
      (node (ref "U1") (pin "2") (pinfunction "AN21_2") (pintype "passive"))
    )
    (net (code "31") (name "LED IO2") (class "Default")
      (node (ref "J1") (pin "4") (pinfunction "C_4") (pintype "passive"))
      (node (ref "Q8") (pin "1") (pinfunction "G_1") (pintype "passive"))
      (node (ref "R3") (pin "2") (pinfunction "2_2") (pintype "passive"))
      (node (ref "R34") (pin "2") (pinfunction "2_2") (pintype "passive"))
      (node (ref "U1") (pin "3") (pinfunction "AN20_3") (pintype "passive"))
    )
    (net (code "32") (name "LED VCC1") (class "Default")
      (node (ref "LED1") (pin "3") (pinfunction "3_3") (pintype "passive"))
      (node (ref "LED10") (pin "3") (pinfunction "3_3") (pintype "passive"))
      (node (ref "LED11") (pin "3") (pinfunction "3_3") (pintype "passive"))
      (node (ref "LED12") (pin "3") (pinfunction "3_3") (pintype "passive"))
      (node (ref "LED2") (pin "3") (pinfunction "3_3") (pintype "passive"))
      (node (ref "LED3") (pin "3") (pinfunction "3_3") (pintype "passive"))
      (node (ref "LED4") (pin "3") (pinfunction "3_3") (pintype "passive"))
      (node (ref "LED5") (pin "3") (pinfunction "3_3") (pintype "passive"))
      (node (ref "LED6") (pin "3") (pinfunction "3_3") (pintype "passive"))
      (node (ref "LED7") (pin "3") (pinfunction "3_3") (pintype "passive"))
      (node (ref "LED8") (pin "3") (pinfunction "3_3") (pintype "passive"))
      (node (ref "LED9") (pin "3") (pinfunction "3_3") (pintype "passive"))
      (node (ref "Q11") (pin "3") (pinfunction "D_3") (pintype "passive"))
      (node (ref "R59") (pin "2") (pinfunction "2_2") (pintype "passive"))
    )
    (net (code "33") (name "LED VCC2") (class "Default")
      (node (ref "LED1") (pin "1") (pinfunction "1_1") (pintype "passive"))
      (node (ref "LED10") (pin "1") (pinfunction "1_1") (pintype "passive"))
      (node (ref "LED11") (pin "1") (pinfunction "1_1") (pintype "passive"))
      (node (ref "LED12") (pin "1") (pinfunction "1_1") (pintype "passive"))
      (node (ref "LED2") (pin "1") (pinfunction "1_1") (pintype "passive"))
      (node (ref "LED3") (pin "1") (pinfunction "1_1") (pintype "passive"))
      (node (ref "LED4") (pin "1") (pinfunction "1_1") (pintype "passive"))
      (node (ref "LED5") (pin "1") (pinfunction "1_1") (pintype "passive"))
      (node (ref "LED6") (pin "1") (pinfunction "1_1") (pintype "passive"))
      (node (ref "LED7") (pin "1") (pinfunction "1_1") (pintype "passive"))
      (node (ref "LED8") (pin "1") (pinfunction "1_1") (pintype "passive"))
      (node (ref "LED9") (pin "1") (pinfunction "1_1") (pintype "passive"))
      (node (ref "Q8") (pin "3") (pinfunction "D_3") (pintype "passive"))
      (node (ref "R60") (pin "1") (pinfunction "1_1") (pintype "passive"))
    )
    (net (code "34") (name "Net-(B13-Pad1)") (class "Default")
      (node (ref "B13") (pin "1") (pinfunction "1_1") (pintype "passive"))
      (node (ref "B14") (pin "1") (pinfunction "1_1") (pintype "passive"))
      (node (ref "R1") (pin "2") (pinfunction "2_2") (pintype "passive"))
      (node (ref "R6") (pin "2") (pinfunction "2_2") (pintype "passive"))
      (node (ref "R7") (pin "1") (pinfunction "1_1") (pintype "passive"))
    )
    (net (code "35") (name "Net-(J2-C)") (class "Default")
      (node (ref "J2") (pin "4") (pinfunction "C_4") (pintype "passive"))
      (node (ref "R38") (pin "1") (pinfunction "1_1") (pintype "passive"))
    )
    (net (code "36") (name "Net-(J2-D)") (class "Default")
      (node (ref "J2") (pin "3") (pinfunction "D_3") (pintype "passive"))
      (node (ref "R34") (pin "1") (pinfunction "1_1") (pintype "passive"))
    )
    (net (code "37") (name "Net-(LED1-Pad2)") (class "Default")
      (node (ref "LED1") (pin "2") (pinfunction "2_2") (pintype "passive"))
      (node (ref "LED1") (pin "4") (pinfunction "4_4") (pintype "passive"))
      (node (ref "R11") (pin "1") (pinfunction "1_1") (pintype "passive"))
    )
    (net (code "38") (name "Net-(LED2-Pad2)") (class "Default")
      (node (ref "LED2") (pin "2") (pinfunction "2_2") (pintype "passive"))
      (node (ref "LED2") (pin "4") (pinfunction "4_4") (pintype "passive"))
      (node (ref "R12") (pin "1") (pinfunction "1_1") (pintype "passive"))
    )
    (net (code "39") (name "Net-(LED3-Pad2)") (class "Default")
      (node (ref "LED3") (pin "2") (pinfunction "2_2") (pintype "passive"))
      (node (ref "LED3") (pin "4") (pinfunction "4_4") (pintype "passive"))
      (node (ref "R13") (pin "1") (pinfunction "1_1") (pintype "passive"))
    )
    (net (code "40") (name "Net-(LED4-Pad2)") (class "Default")
      (node (ref "LED4") (pin "2") (pinfunction "2_2") (pintype "passive"))
      (node (ref "LED4") (pin "4") (pinfunction "4_4") (pintype "passive"))
      (node (ref "R8") (pin "1") (pinfunction "1_1") (pintype "passive"))
    )
    (net (code "41") (name "Net-(LED5-Pad2)") (class "Default")
      (node (ref "LED5") (pin "2") (pinfunction "2_2") (pintype "passive"))
      (node (ref "LED5") (pin "4") (pinfunction "4_4") (pintype "passive"))
      (node (ref "R17") (pin "1") (pinfunction "1_1") (pintype "passive"))
    )
    (net (code "42") (name "Net-(LED6-Pad2)") (class "Default")
      (node (ref "LED6") (pin "2") (pinfunction "2_2") (pintype "passive"))
      (node (ref "LED6") (pin "4") (pinfunction "4_4") (pintype "passive"))
      (node (ref "R22") (pin "1") (pinfunction "1_1") (pintype "passive"))
    )
    (net (code "43") (name "Net-(LED7-Pad2)") (class "Default")
      (node (ref "LED7") (pin "2") (pinfunction "2_2") (pintype "passive"))
      (node (ref "LED7") (pin "4") (pinfunction "4_4") (pintype "passive"))
      (node (ref "R14") (pin "2") (pinfunction "2_2") (pintype "passive"))
    )
    (net (code "44") (name "Net-(LED8-Pad2)") (class "Default")
      (node (ref "LED8") (pin "2") (pinfunction "2_2") (pintype "passive"))
      (node (ref "LED8") (pin "4") (pinfunction "4_4") (pintype "passive"))
      (node (ref "R16") (pin "2") (pinfunction "2_2") (pintype "passive"))
    )
    (net (code "45") (name "Net-(LED9-Pad2)") (class "Default")
      (node (ref "LED9") (pin "2") (pinfunction "2_2") (pintype "passive"))
      (node (ref "LED9") (pin "4") (pinfunction "4_4") (pintype "passive"))
      (node (ref "R24") (pin "2") (pinfunction "2_2") (pintype "passive"))
    )
    (net (code "46") (name "Net-(LED10-Pad2)") (class "Default")
      (node (ref "LED10") (pin "2") (pinfunction "2_2") (pintype "passive"))
      (node (ref "LED10") (pin "4") (pinfunction "4_4") (pintype "passive"))
      (node (ref "R27") (pin "2") (pinfunction "2_2") (pintype "passive"))
    )
    (net (code "47") (name "Net-(LED11-Pad2)") (class "Default")
      (node (ref "LED11") (pin "2") (pinfunction "2_2") (pintype "passive"))
      (node (ref "LED11") (pin "4") (pinfunction "4_4") (pintype "passive"))
      (node (ref "R28") (pin "2") (pinfunction "2_2") (pintype "passive"))
    )
    (net (code "48") (name "Net-(LED12-Pad2)") (class "Default")
      (node (ref "LED12") (pin "2") (pinfunction "2_2") (pintype "passive"))
      (node (ref "LED12") (pin "4") (pinfunction "4_4") (pintype "passive"))
      (node (ref "R33") (pin "2") (pinfunction "2_2") (pintype "passive"))
    )
    (net (code "49") (name "Net-(Q1-D)") (class "Default")
      (node (ref "B1") (pin "1") (pinfunction "1_1") (pintype "passive"))
      (node (ref "Q1") (pin "3") (pinfunction "D_3") (pintype "passive"))
      (node (ref "R2") (pin "1") (pinfunction "1_1") (pintype "passive"))
      (node (ref "R4") (pin "2") (pinfunction "2_2") (pintype "passive"))
    )
    (net (code "50") (name "Net-(Q2-D)") (class "Default")
      (node (ref "B2") (pin "1") (pinfunction "1_1") (pintype "passive"))
      (node (ref "Q2") (pin "3") (pinfunction "D_3") (pintype "passive"))
      (node (ref "R10") (pin "2") (pinfunction "2_2") (pintype "passive"))
      (node (ref "R57") (pin "1") (pinfunction "1_1") (pintype "passive"))
    )
    (net (code "51") (name "Net-(Q4-D)") (class "Default")
      (node (ref "B3") (pin "1") (pinfunction "1_1") (pintype "passive"))
      (node (ref "Q4") (pin "3") (pinfunction "D_3") (pintype "passive"))
      (node (ref "R18") (pin "1") (pinfunction "1_1") (pintype "passive"))
      (node (ref "R20") (pin "2") (pinfunction "2_2") (pintype "passive"))
    )
    (net (code "52") (name "Net-(Q5-D)") (class "Default")
      (node (ref "B8") (pin "1") (pinfunction "1_1") (pintype "passive"))
      (node (ref "Q5") (pin "3") (pinfunction "D_3") (pintype "passive"))
      (node (ref "R19") (pin "1") (pinfunction "1_1") (pintype "passive"))
      (node (ref "R21") (pin "2") (pinfunction "2_2") (pintype "passive"))
    )
    (net (code "53") (name "Net-(Q6-D)") (class "Default")
      (node (ref "B4") (pin "1") (pinfunction "1_1") (pintype "passive"))
      (node (ref "Q6") (pin "3") (pinfunction "D_3") (pintype "passive"))
      (node (ref "R29") (pin "1") (pinfunction "1_1") (pintype "passive"))
      (node (ref "R31") (pin "2") (pinfunction "2_2") (pintype "passive"))
    )
    (net (code "54") (name "Net-(Q7-D)") (class "Default")
      (node (ref "B7") (pin "1") (pinfunction "1_1") (pintype "passive"))
      (node (ref "Q7") (pin "3") (pinfunction "D_3") (pintype "passive"))
      (node (ref "R30") (pin "1") (pinfunction "1_1") (pintype "passive"))
      (node (ref "R32") (pin "2") (pinfunction "2_2") (pintype "passive"))
    )
    (net (code "55") (name "Net-(Q9-D)") (class "Default")
      (node (ref "B6") (pin "1") (pinfunction "1_1") (pintype "passive"))
      (node (ref "Q9") (pin "3") (pinfunction "D_3") (pintype "passive"))
      (node (ref "R40") (pin "1") (pinfunction "1_1") (pintype "passive"))
      (node (ref "R41") (pin "2") (pinfunction "2_2") (pintype "passive"))
    )
    (net (code "56") (name "Net-(Q10-D)") (class "Default")
      (node (ref "B5") (pin "1") (pinfunction "1_1") (pintype "passive"))
      (node (ref "Q10") (pin "3") (pinfunction "D_3") (pintype "passive"))
      (node (ref "R45") (pin "1") (pinfunction "1_1") (pintype "passive"))
      (node (ref "R46") (pin "2") (pinfunction "2_2") (pintype "passive"))
    )
    (net (code "57") (name "Net-(Q13-D)") (class "Default")
      (node (ref "B9") (pin "1") (pinfunction "1_1") (pintype "passive"))
      (node (ref "Q13") (pin "3") (pinfunction "D_3") (pintype "passive"))
      (node (ref "R37") (pin "2") (pinfunction "2_2") (pintype "passive"))
      (node (ref "R9") (pin "1") (pinfunction "1_1") (pintype "passive"))
    )
    (net (code "58") (name "Net-(Q14-D)") (class "Default")
      (node (ref "B10") (pin "1") (pinfunction "1_1") (pintype "passive"))
      (node (ref "Q14") (pin "3") (pinfunction "D_3") (pintype "passive"))
      (node (ref "R36") (pin "1") (pinfunction "1_1") (pintype "passive"))
      (node (ref "R39") (pin "2") (pinfunction "2_2") (pintype "passive"))
    )
    (net (code "59") (name "Net-(Q15-D)") (class "Default")
      (node (ref "B11") (pin "1") (pinfunction "1_1") (pintype "passive"))
      (node (ref "Q15") (pin "3") (pinfunction "D_3") (pintype "passive"))
      (node (ref "R50") (pin "1") (pinfunction "1_1") (pintype "passive"))
      (node (ref "R52") (pin "2") (pinfunction "2_2") (pintype "passive"))
    )
    (net (code "60") (name "Net-(Q16-D)") (class "Default")
      (node (ref "B12") (pin "1") (pinfunction "1_1") (pintype "passive"))
      (node (ref "Q16") (pin "3") (pinfunction "D_3") (pintype "passive"))
      (node (ref "R51") (pin "1") (pinfunction "1_1") (pintype "passive"))
      (node (ref "R53") (pin "2") (pinfunction "2_2") (pintype "passive"))
    )
    (net (code "61") (name "Net-(Q17-G)") (class "Default")
      (node (ref "Q17") (pin "4") (pinfunction "G_4") (pintype "passive"))
      (node (ref "Q19") (pin "3") (pinfunction "C_3") (pintype "passive"))
      (node (ref "R56") (pin "1") (pinfunction "1_1") (pintype "passive"))
    )
    (net (code "62") (name "Net-(Q19-B)") (class "Default")
      (node (ref "Q19") (pin "1") (pinfunction "B_1") (pintype "passive"))
      (node (ref "R35") (pin "2") (pinfunction "2_2") (pintype "passive"))
      (node (ref "R5") (pin "2") (pinfunction "2_2") (pintype "passive"))
    )
    (net (code "63") (name "Net-(TYPEC1-CC1)") (class "Default")
      (node (ref "R23") (pin "2") (pinfunction "2_2") (pintype "passive"))
      (node (ref "TYPEC1") (pin "3") (pinfunction "CC1_3") (pintype "passive"))
    )
    (net (code "64") (name "Net-(TYPEC1-CC2)") (class "Default")
      (node (ref "R15") (pin "1") (pinfunction "1_1") (pintype "passive"))
      (node (ref "TYPEC1") (pin "4") (pinfunction "CC2_4") (pintype "passive"))
    )
    (net (code "65") (name "Net-(U1-VDD)") (class "Default")
      (node (ref "C12") (pin "2") (pinfunction "2_2") (pintype "passive"))
      (node (ref "C6") (pin "2") (pinfunction "2_2") (pintype "passive"))
      (node (ref "R48") (pin "1") (pinfunction "1_1") (pintype "passive"))
      (node (ref "R49") (pin "1") (pinfunction "1_1") (pintype "passive"))
      (node (ref "U1") (pin "1") (pinfunction "VDD_1") (pintype "passive"))
    )
    (net (code "66") (name "VCC") (class "Default")
      (node (ref "J1") (pin "1") (pinfunction "V_1") (pintype "passive"))
      (node (ref "J2") (pin "1") (pinfunction "V_1") (pintype "passive"))
      (node (ref "Q11") (pin "2") (pinfunction "S_2") (pintype "passive"))
      (node (ref "Q17") (pin "1") (pinfunction "S_1") (pintype "passive"))
      (node (ref "Q17") (pin "2") (pinfunction "S_2") (pintype "passive"))
      (node (ref "Q17") (pin "3") (pinfunction "S_3") (pintype "passive"))
      (node (ref "Q3") (pin "1") (pinfunction "S_1") (pintype "passive"))
      (node (ref "Q3") (pin "2") (pinfunction "S_2") (pintype "passive"))
      (node (ref "Q3") (pin "3") (pinfunction "S_3") (pintype "passive"))
      (node (ref "Q8") (pin "2") (pinfunction "S_2") (pintype "passive"))
      (node (ref "R18") (pin "2") (pinfunction "2_2") (pintype "passive"))
      (node (ref "R19") (pin "2") (pinfunction "2_2") (pintype "passive"))
      (node (ref "R2") (pin "2") (pinfunction "2_2") (pintype "passive"))
      (node (ref "R25") (pin "1") (pinfunction "1_1") (pintype "passive"))
      (node (ref "R26") (pin "2") (pinfunction "2_2") (pintype "passive"))
      (node (ref "R29") (pin "2") (pinfunction "2_2") (pintype "passive"))
      (node (ref "R3") (pin "1") (pinfunction "1_1") (pintype "passive"))
      (node (ref "R30") (pin "2") (pinfunction "2_2") (pintype "passive"))
      (node (ref "R36") (pin "2") (pinfunction "2_2") (pintype "passive"))
      (node (ref "R40") (pin "2") (pinfunction "2_2") (pintype "passive"))
      (node (ref "R45") (pin "2") (pinfunction "2_2") (pintype "passive"))
      (node (ref "R49") (pin "2") (pinfunction "2_2") (pintype "passive"))
      (node (ref "R50") (pin "2") (pinfunction "2_2") (pintype "passive"))
      (node (ref "R51") (pin "2") (pinfunction "2_2") (pintype "passive"))
      (node (ref "R56") (pin "2") (pinfunction "2_2") (pintype "passive"))
      (node (ref "R57") (pin "2") (pinfunction "2_2") (pintype "passive"))
      (node (ref "R61") (pin "1") (pinfunction "1_1") (pintype "passive"))
      (node (ref "R9") (pin "2") (pinfunction "2_2") (pintype "passive"))
    )
    (net (code "67") (name "VCC1") (class "Default")
      (node (ref "C3") (pin "2") (pinfunction "2_2") (pintype "passive"))
      (node (ref "C5") (pin "2") (pinfunction "2_2") (pintype "passive"))
      (node (ref "Q1") (pin "2") (pinfunction "S_2") (pintype "passive"))
      (node (ref "Q10") (pin "2") (pinfunction "S_2") (pintype "passive"))
      (node (ref "Q13") (pin "2") (pinfunction "S_2") (pintype "passive"))
      (node (ref "Q14") (pin "2") (pinfunction "S_2") (pintype "passive"))
      (node (ref "Q15") (pin "2") (pinfunction "S_2") (pintype "passive"))
      (node (ref "Q16") (pin "2") (pinfunction "S_2") (pintype "passive"))
      (node (ref "Q2") (pin "2") (pinfunction "S_2") (pintype "passive"))
      (node (ref "Q3") (pin "5") (pinfunction "D_5") (pintype "passive"))
      (node (ref "Q3") (pin "6") (pinfunction "D_6") (pintype "passive"))
      (node (ref "Q3") (pin "7") (pinfunction "D_7") (pintype "passive"))
      (node (ref "Q3") (pin "8") (pinfunction "D_8") (pintype "passive"))
      (node (ref "Q4") (pin "2") (pinfunction "S_2") (pintype "passive"))
      (node (ref "Q5") (pin "2") (pinfunction "S_2") (pintype "passive"))
      (node (ref "Q6") (pin "2") (pinfunction "S_2") (pintype "passive"))
      (node (ref "Q7") (pin "2") (pinfunction "S_2") (pintype "passive"))
      (node (ref "Q9") (pin "2") (pinfunction "S_2") (pintype "passive"))
      (node (ref "R26") (pin "1") (pinfunction "1_1") (pintype "passive"))
      (node (ref "R62") (pin "1") (pinfunction "1_1") (pintype "passive"))
      (node (ref "R63") (pin "1") (pinfunction "1_1") (pintype "passive"))
      (node (ref "R64") (pin "1") (pinfunction "1_1") (pintype "passive"))
      (node (ref "R65") (pin "1") (pinfunction "1_1") (pintype "passive"))
      (node (ref "R66") (pin "1") (pinfunction "1_1") (pintype "passive"))
      (node (ref "R67") (pin "1") (pinfunction "1_1") (pintype "passive"))
      (node (ref "R68") (pin "1") (pinfunction "1_1") (pintype "passive"))
      (node (ref "R69") (pin "1") (pinfunction "1_1") (pintype "passive"))
      (node (ref "R70") (pin "1") (pinfunction "1_1") (pintype "passive"))
      (node (ref "R71") (pin "1") (pinfunction "1_1") (pintype "passive"))
      (node (ref "R72") (pin "1") (pinfunction "1_1") (pintype "passive"))
      (node (ref "R73") (pin "1") (pinfunction "1_1") (pintype "passive"))
    )
    (net (code "68") (name "VCC5V") (class "Default")
      (node (ref "C1") (pin "2") (pinfunction "2_2") (pintype "passive"))
      (node (ref "C2") (pin "2") (pinfunction "2_2") (pintype "passive"))
      (node (ref "Q17") (pin "5") (pinfunction "D_5") (pintype "passive"))
      (node (ref "Q17") (pin "6") (pinfunction "D_6") (pintype "passive"))
      (node (ref "Q17") (pin "7") (pinfunction "D_7") (pintype "passive"))
      (node (ref "Q17") (pin "8") (pinfunction "D_8") (pintype "passive"))
      (node (ref "R5") (pin "1") (pinfunction "1_1") (pintype "passive"))
      (node (ref "TVS1") (pin "2") (pinfunction "K_2") (pintype "passive"))
      (node (ref "TYPEC1") (pin "2") (pinfunction "VBUS_2") (pintype "passive"))
      (node (ref "TYPEC1") (pin "5") (pinfunction "VBUS_5") (pintype "passive"))
    )
  )
)
